# Interboard.net
KiCad netlist of a schematic drawn in Altium Designer
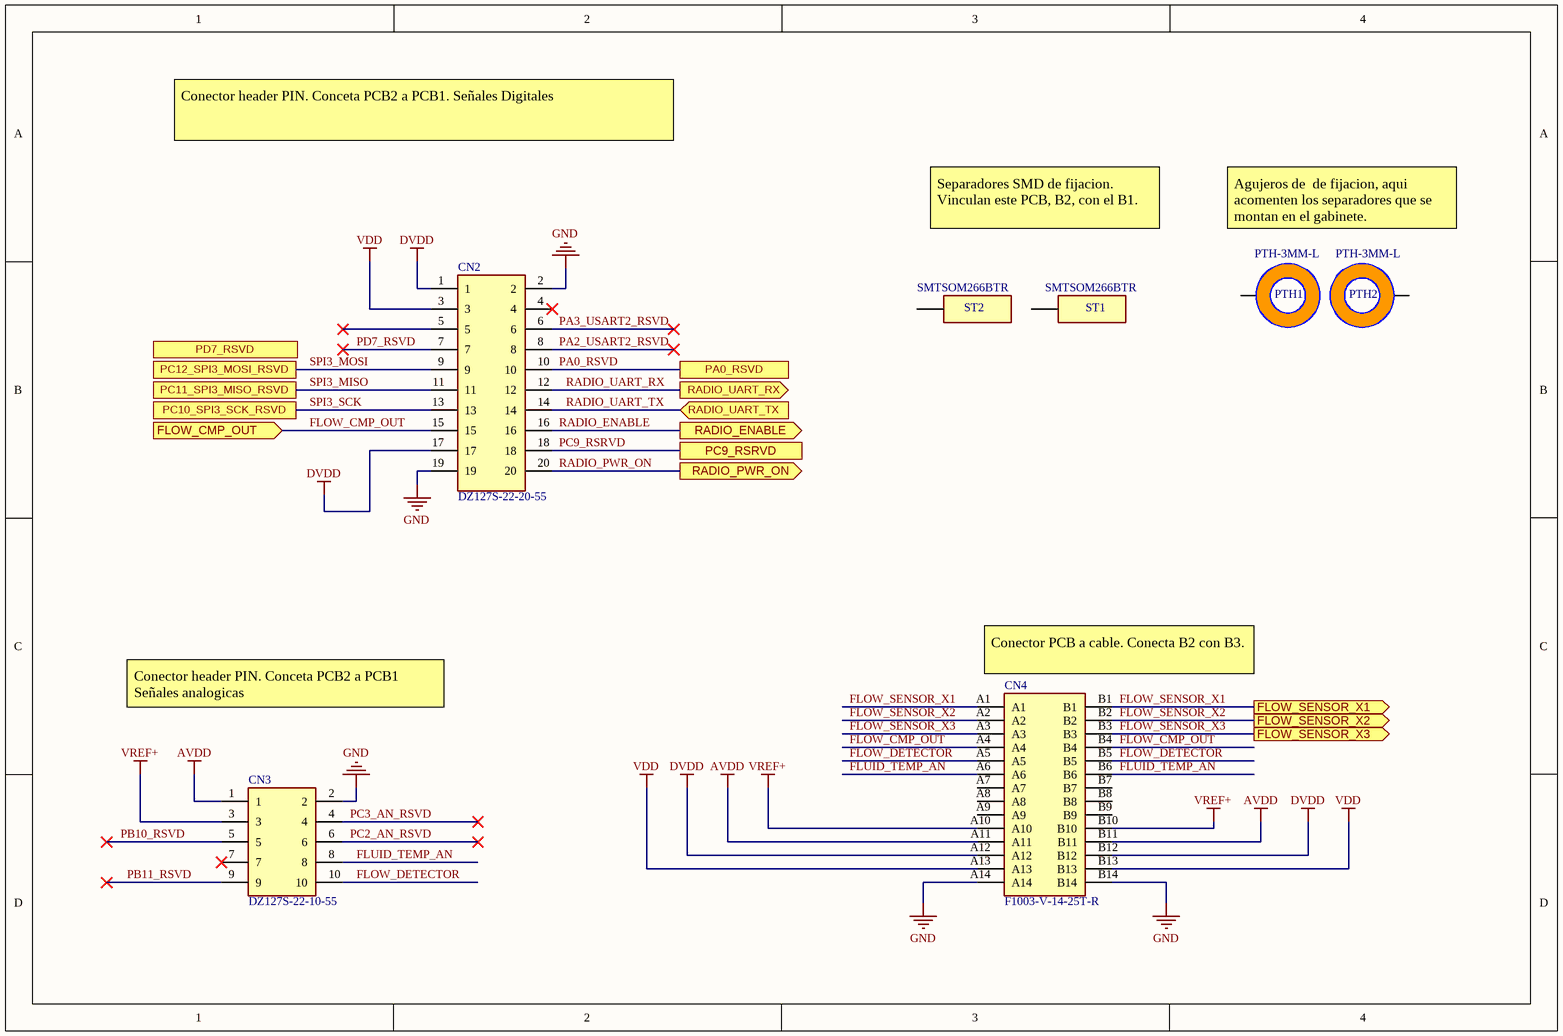
[diagram p0: Interboard.SchDoc]

(export (version "E")
  (design (tool "Eeschema 10.0.6"))
  (components
    (comp (ref "CN2")
      (value "DZ127S-22-20-55")
      (footprint "DZ127S-22-20-55")
      (description "Header Pin SMD 1.27mm 2x10")
      (fields
        (field (name "MOUSER PART NUMBER") "200-SFMC11002LD")
        (field (name "MANUFACTURER_PART_NUMBER") "SFMC-110-02-L-D")
      )
      (libsource (lib "flowmeet") (part "DZ127S-22-20-55"))
    )
    (comp (ref "CN3")
      (value "DZ127S-22-10-55")
      (footprint "DZ127S-22-10-55")
      (description "Header PIN SMD 1.27mm 2x5")
      (fields
        (field (name "MANUFACTURER") "Dealon")
        (field (name "MANUFACTURER PART NUMBER") "DW127S-22-10-43")
      )
      (libsource (lib "flowmeet") (part "DZ127S-22-10-55"))
    )
    (comp (ref "CN4")
      (value "F1003-V-14-25T-R")
      (footprint "F1003-V-14-25T-R")
      (description "14 Position FFC, FPC Connector Contacts, Vertical - 1 Sided 0.039\" (1.00mm) Surface Mount")
      (fields (field (name "MANUFACTURER") "XFCN") (field (name "VENDOR PART NUMBER") "C2764805"))
      (libsource (lib "flowmeet") (part "F1003-V-14-25T-R"))
    )
    (comp (ref "PTH1")
      (value "PTH-3MM-L")
      (footprint "PTH_M3_L")
      (description "Montaje M3. algo de holgura y buena corona.")
      (libsource (lib "flowmeet") (part "PTH-3MM-L"))
    )
    (comp (ref "PTH2")
      (value "PTH-3MM-L")
      (footprint "PTH_M3_L")
      (description "Montaje M3. algo de holgura y buena corona.")
      (libsource (lib "flowmeet") (part "PTH-3MM-L"))
    )
    (comp (ref "ST1")
      (value "SMTSOM266BTR")
      (footprint "SMTSOM230BTR")
      (description "Standoffs & Spacers SURFACE MOUNT STANDOFF")
      (fields (field (name "MANUFACTURER") "Yiyuan"))
      (libsource (lib "flowmeet") (part "SMTSOM266BTR"))
    )
    (comp (ref "ST2")
      (value "SMTSOM266BTR")
      (footprint "SMTSOM230BTR")
      (description "Standoffs & Spacers SURFACE MOUNT STANDOFF")
      (fields (field (name "MANUFACTURER") "Yiyuan"))
      (libsource (lib "flowmeet") (part "SMTSOM266BTR"))
    )
  )
  (nets
    (net (code "1") (name "/FLOW_CMP_OUT") (class "Default")
      (node (ref "CN2") (pin "15") (pinfunction "15_15") (pintype "passive"))
      (node (ref "CN4") (pin "A4") (pinfunction "A4_A4") (pintype "passive"))
      (node (ref "CN4") (pin "B4") (pinfunction "B4_B4") (pintype "passive"))
    )
    (net (code "2") (name "/FLOW_DETECTOR") (class "Default")
      (node (ref "CN3") (pin "10") (pinfunction "10_10") (pintype "passive"))
      (node (ref "CN4") (pin "A5") (pinfunction "A5_A5") (pintype "passive"))
      (node (ref "CN4") (pin "B5") (pinfunction "B5_B5") (pintype "passive"))
    )
    (net (code "3") (name "/FLOW_SENSOR_X1") (class "Default")
      (node (ref "CN4") (pin "A1") (pinfunction "A1_A1") (pintype "passive"))
      (node (ref "CN4") (pin "B1") (pinfunction "B1_B1") (pintype "passive"))
    )
    (net (code "4") (name "/FLOW_SENSOR_X2") (class "Default")
      (node (ref "CN4") (pin "A2") (pinfunction "A2_A2") (pintype "passive"))
      (node (ref "CN4") (pin "B2") (pinfunction "B2_B2") (pintype "passive"))
    )
    (net (code "5") (name "/FLOW_SENSOR_X3") (class "Default")
      (node (ref "CN4") (pin "A3") (pinfunction "A3_A3") (pintype "passive"))
      (node (ref "CN4") (pin "B3") (pinfunction "B3_B3") (pintype "passive"))
    )
    (net (code "6") (name "/FLUID_TEMP_AN") (class "Default")
      (node (ref "CN3") (pin "8") (pinfunction "8_8") (pintype "passive"))
      (node (ref "CN4") (pin "A6") (pinfunction "A6_A6") (pintype "passive"))
      (node (ref "CN4") (pin "B6") (pinfunction "B6_B6") (pintype "passive"))
    )
    (net (code "7") (name "/PA0_RSVD") (class "Default")
      (node (ref "CN2") (pin "10") (pinfunction "10_10") (pintype "passive"))
    )
    (net (code "8") (name "/PA2_USART2_RSVD") (class "Default")
      (node (ref "CN2") (pin "8") (pinfunction "8_8") (pintype "passive+no_connect"))
    )
    (net (code "9") (name "/PA3_USART2_RSVD") (class "Default")
      (node (ref "CN2") (pin "6") (pinfunction "6_6") (pintype "passive+no_connect"))
    )
    (net (code "10") (name "/PB10_RSVD") (class "Default")
      (node (ref "CN3") (pin "5") (pinfunction "5_5") (pintype "passive+no_connect"))
    )
    (net (code "11") (name "/PB11_RSVD") (class "Default")
      (node (ref "CN3") (pin "9") (pinfunction "9_9") (pintype "passive+no_connect"))
    )
    (net (code "12") (name "/PC2_AN_RSVD") (class "Default")
      (node (ref "CN3") (pin "6") (pinfunction "6_6") (pintype "passive+no_connect"))
    )
    (net (code "13") (name "/PC3_AN_RSVD") (class "Default")
      (node (ref "CN3") (pin "4") (pinfunction "4_4") (pintype "passive+no_connect"))
    )
    (net (code "14") (name "/PC9_RSRVD") (class "Default")
      (node (ref "CN2") (pin "18") (pinfunction "18_18") (pintype "passive"))
    )
    (net (code "15") (name "/PD7_RSVD") (class "Default")
      (node (ref "CN2") (pin "7") (pinfunction "7_7") (pintype "passive+no_connect"))
    )
    (net (code "16") (name "/RADIO_ENABLE") (class "Default")
      (node (ref "CN2") (pin "16") (pinfunction "16_16") (pintype "passive"))
    )
    (net (code "17") (name "/RADIO_PWR_ON") (class "Default")
      (node (ref "CN2") (pin "20") (pinfunction "20_20") (pintype "passive"))
    )
    (net (code "18") (name "/RADIO_UART_RX") (class "Default")
      (node (ref "CN2") (pin "12") (pinfunction "12_12") (pintype "passive"))
    )
    (net (code "19") (name "/RADIO_UART_TX") (class "Default")
      (node (ref "CN2") (pin "14") (pinfunction "14_14") (pintype "passive"))
    )
    (net (code "20") (name "/SPI3_MISO") (class "Default")
      (node (ref "CN2") (pin "11") (pinfunction "11_11") (pintype "passive"))
    )
    (net (code "21") (name "/SPI3_MOSI") (class "Default")
      (node (ref "CN2") (pin "9") (pinfunction "9_9") (pintype "passive"))
    )
    (net (code "22") (name "/SPI3_SCK") (class "Default")
      (node (ref "CN2") (pin "13") (pinfunction "13_13") (pintype "passive"))
    )
    (net (code "23") (name "AVDD") (class "Default")
      (node (ref "CN3") (pin "1") (pinfunction "1_1") (pintype "passive"))
      (node (ref "CN4") (pin "A11") (pinfunction "A11_A11") (pintype "passive"))
      (node (ref "CN4") (pin "B11") (pinfunction "B11_B11") (pintype "passive"))
    )
    (net (code "24") (name "DVDD") (class "Default")
      (node (ref "CN2") (pin "1") (pinfunction "1_1") (pintype "passive"))
      (node (ref "CN2") (pin "17") (pinfunction "17_17") (pintype "passive"))
      (node (ref "CN4") (pin "A12") (pinfunction "A12_A12") (pintype "passive"))
      (node (ref "CN4") (pin "B12") (pinfunction "B12_B12") (pintype "passive"))
    )
    (net (code "25") (name "GND") (class "Default")
      (node (ref "CN2") (pin "19") (pinfunction "19_19") (pintype "passive"))
      (node (ref "CN2") (pin "2") (pinfunction "2_2") (pintype "passive"))
      (node (ref "CN3") (pin "2") (pinfunction "2_2") (pintype "passive"))
      (node (ref "CN4") (pin "A14") (pinfunction "A14_A14") (pintype "passive"))
      (node (ref "CN4") (pin "B14") (pinfunction "B14_B14") (pintype "passive"))
    )
    (net (code "26") (name "VDD") (class "Default")
      (node (ref "CN2") (pin "3") (pinfunction "3_3") (pintype "passive"))
      (node (ref "CN4") (pin "A13") (pinfunction "A13_A13") (pintype "passive"))
      (node (ref "CN4") (pin "B13") (pinfunction "B13_B13") (pintype "passive"))
    )
    (net (code "27") (name "VREF+") (class "Default")
      (node (ref "CN3") (pin "3") (pinfunction "3_3") (pintype "passive"))
      (node (ref "CN4") (pin "A10") (pinfunction "A10_A10") (pintype "passive"))
      (node (ref "CN4") (pin "B10") (pinfunction "B10_B10") (pintype "passive"))
    )
    (net (code "28") (name "unconnected-(CN2-Pad4)") (class "Default")
      (node (ref "CN2") (pin "4") (pinfunction "4_4") (pintype "passive+no_connect"))
    )
    (net (code "29") (name "unconnected-(CN2-Pad5)") (class "Default")
      (node (ref "CN2") (pin "5") (pinfunction "5_5") (pintype "passive+no_connect"))
    )
    (net (code "30") (name "unconnected-(CN3-Pad7)") (class "Default")
      (node (ref "CN3") (pin "7") (pinfunction "7_7") (pintype "passive+no_connect"))
    )
    (net (code "31") (name "unconnected-(CN4-PadA7)") (class "Default")
      (node (ref "CN4") (pin "A7") (pinfunction "A7_A7") (pintype "passive"))
    )
    (net (code "32") (name "unconnected-(CN4-PadA8)") (class "Default")
      (node (ref "CN4") (pin "A8") (pinfunction "A8_A8") (pintype "passive"))
    )
    (net (code "33") (name "unconnected-(CN4-PadA9)") (class "Default")
      (node (ref "CN4") (pin "A9") (pinfunction "A9_A9") (pintype "passive"))
    )
    (net (code "34") (name "unconnected-(CN4-PadB7)") (class "Default")
      (node (ref "CN4") (pin "B7") (pinfunction "B7_B7") (pintype "passive"))
    )
    (net (code "35") (name "unconnected-(CN4-PadB8)") (class "Default")
      (node (ref "CN4") (pin "B8") (pinfunction "B8_B8") (pintype "passive"))
    )
    (net (code "36") (name "unconnected-(CN4-PadB9)") (class "Default")
      (node (ref "CN4") (pin "B9") (pinfunction "B9_B9") (pintype "passive"))
    )
    (net (code "37") (name "unconnected-(PTH1-Pad1)") (class "Default")
      (node (ref "PTH1") (pin "1") (pinfunction "1_1") (pintype "passive"))
    )
    (net (code "38") (name "unconnected-(PTH2-Pad1)") (class "Default")
      (node (ref "PTH2") (pin "1") (pinfunction "1_1") (pintype "passive"))
    )
    (net (code "39") (name "unconnected-(ST1-PadMH1)") (class "Default")
      (node (ref "ST1") (pin "MH1") (pinfunction "MH1_MH1") (pintype "passive"))
    )
    (net (code "40") (name "unconnected-(ST2-PadMH1)") (class "Default")
      (node (ref "ST2") (pin "MH1") (pinfunction "MH1_MH1") (pintype "passive"))
    )
  )
)
